# Foot_Controller.net
KiCad netlist of a schematic drawn in EAGLE
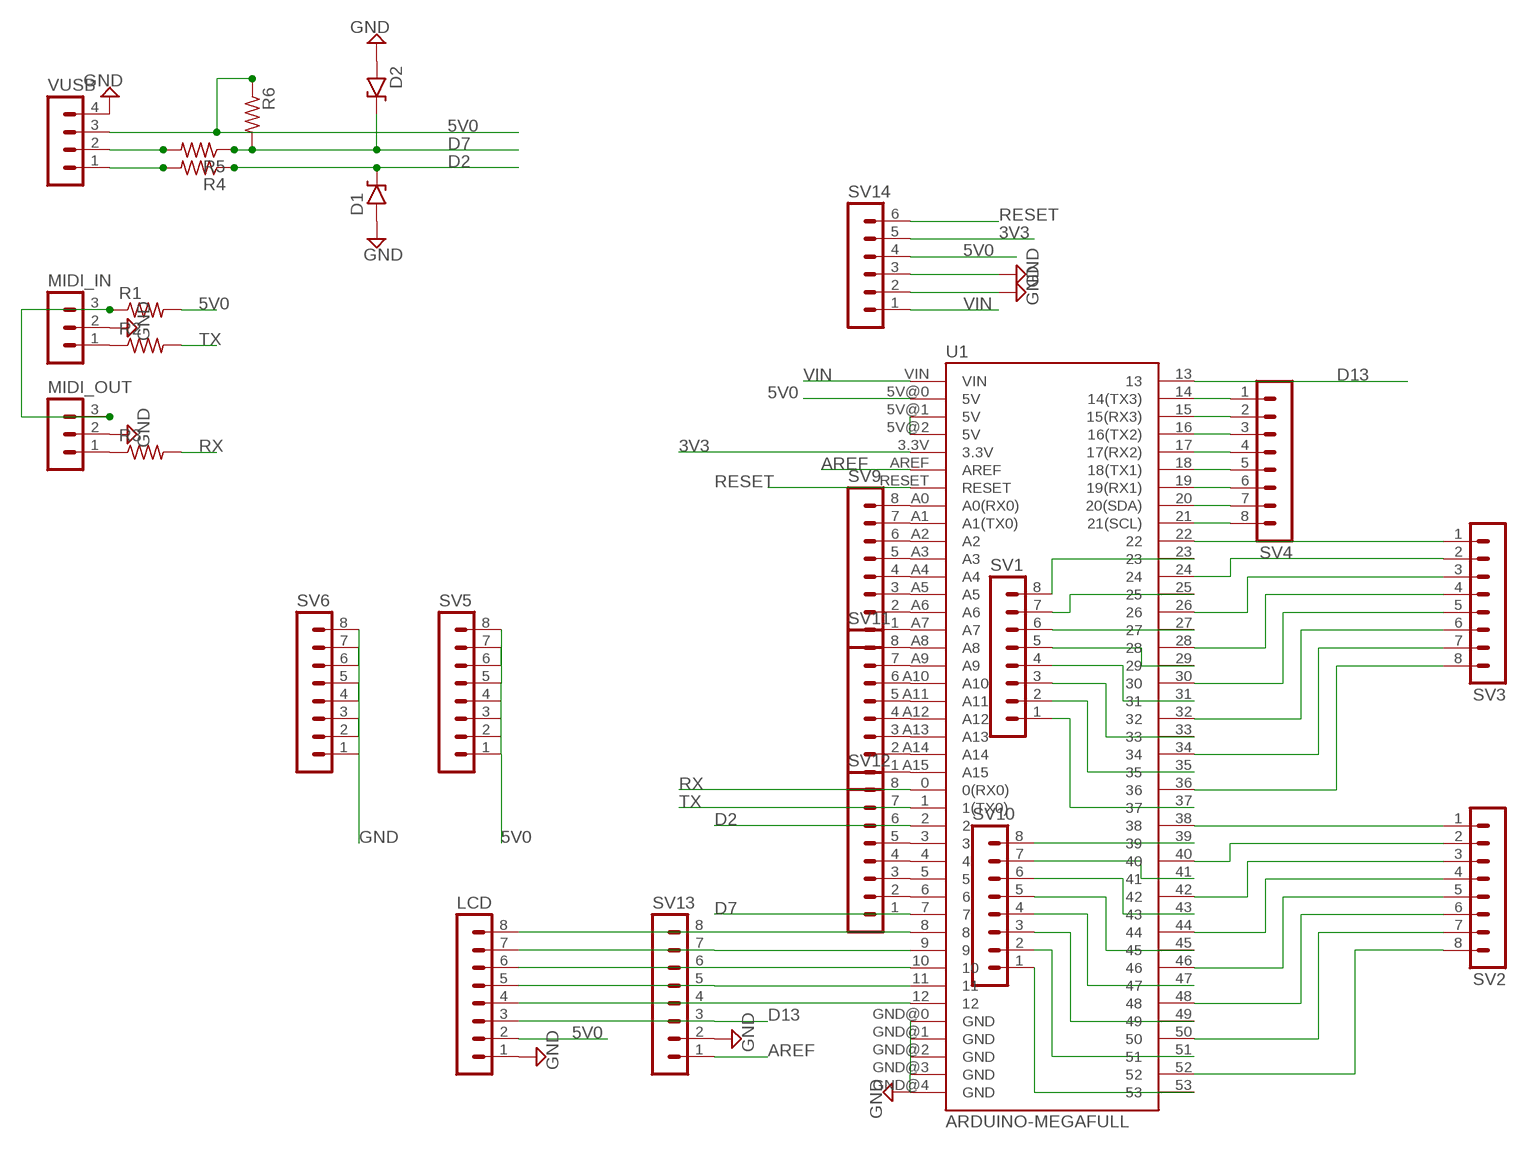
[diagram p0: schematic, sheet 1]

(export (version "E")
  (design (tool "Eeschema 10.0.6"))
  (components
    (comp (ref "D1")
      (value "1N9ZENER")
      (footprint "eagle-import:DO35-3")
      (libsource (lib "eagle-import") (part "1N9ZENER"))
    )
    (comp (ref "D2")
      (value "1N9ZENER")
      (footprint "eagle-import:DO35-3")
      (libsource (lib "eagle-import") (part "1N9ZENER"))
    )
    (comp (ref "LCD")
      (value "MA08-1")
      (footprint "eagle-import:MA08-1")
      (libsource (lib "eagle-import") (part "MA08-1"))
    )
    (comp (ref "MIDI_IN")
      (value "MA03-1")
      (footprint "eagle-import:MA03-1")
      (libsource (lib "eagle-import") (part "MA03-1"))
    )
    (comp (ref "MIDI_OUT")
      (value "MA03-1")
      (footprint "eagle-import:MA03-1")
      (libsource (lib "eagle-import") (part "MA03-1"))
    )
    (comp (ref "R1")
      (value "6MM.3")
      (footprint "eagle-import:R0207_3")
      (libsource (lib "eagle-import") (part "6MM.3"))
    )
    (comp (ref "R2")
      (value "6MM.3")
      (footprint "eagle-import:R0207_3")
      (libsource (lib "eagle-import") (part "6MM.3"))
    )
    (comp (ref "R3")
      (value "6MM.3")
      (footprint "eagle-import:R0207_3")
      (libsource (lib "eagle-import") (part "6MM.3"))
    )
    (comp (ref "R4")
      (value "6MM.3")
      (footprint "eagle-import:R0207_3")
      (libsource (lib "eagle-import") (part "6MM.3"))
    )
    (comp (ref "R5")
      (value "6MM.3")
      (footprint "eagle-import:R0207_3")
      (libsource (lib "eagle-import") (part "6MM.3"))
    )
    (comp (ref "R6")
      (value "6MM.3")
      (footprint "eagle-import:R0207_3")
      (libsource (lib "eagle-import") (part "6MM.3"))
    )
    (comp (ref "SV1")
      (value "MA08-1")
      (footprint "eagle-import:MA08-1")
      (libsource (lib "eagle-import") (part "MA08-1"))
    )
    (comp (ref "SV2")
      (value "MA08-1")
      (footprint "eagle-import:MA08-1")
      (libsource (lib "eagle-import") (part "MA08-1"))
    )
    (comp (ref "SV3")
      (value "MA08-1")
      (footprint "eagle-import:MA08-1")
      (libsource (lib "eagle-import") (part "MA08-1"))
    )
    (comp (ref "SV4")
      (value "MA08-1")
      (footprint "eagle-import:MA08-1")
      (libsource (lib "eagle-import") (part "MA08-1"))
    )
    (comp (ref "SV5")
      (value "MA08-1")
      (footprint "eagle-import:MA08-1")
      (libsource (lib "eagle-import") (part "MA08-1"))
    )
    (comp (ref "SV6")
      (value "MA08-1")
      (footprint "eagle-import:MA08-1")
      (libsource (lib "eagle-import") (part "MA08-1"))
    )
    (comp (ref "SV9")
      (value "MA08-1")
      (footprint "eagle-import:MA08-1")
      (libsource (lib "eagle-import") (part "MA08-1"))
    )
    (comp (ref "SV10")
      (value "MA08-1")
      (footprint "eagle-import:MA08-1")
      (libsource (lib "eagle-import") (part "MA08-1"))
    )
    (comp (ref "SV11")
      (value "MA08-1")
      (footprint "eagle-import:MA08-1")
      (libsource (lib "eagle-import") (part "MA08-1"))
    )
    (comp (ref "SV12")
      (value "MA08-1")
      (footprint "eagle-import:MA08-1")
      (libsource (lib "eagle-import") (part "MA08-1"))
    )
    (comp (ref "SV13")
      (value "MA08-1")
      (footprint "eagle-import:MA08-1")
      (libsource (lib "eagle-import") (part "MA08-1"))
    )
    (comp (ref "SV14")
      (value "MA06-1")
      (footprint "eagle-import:MA06-1")
      (libsource (lib "eagle-import") (part "MA06-1"))
    )
    (comp (ref "U1")
      (value "ARDUINO-MEGAFULL")
      (footprint "eagle-import:ARDUINO_MEGA")
      (libsource (lib "eagle-import") (part "ARDUINO-MEGAFULL"))
    )
    (comp (ref "VUSB")
      (value "MA04-1")
      (footprint "eagle-import:MA04-1")
      (libsource (lib "eagle-import") (part "MA04-1"))
    )
  )
  (nets
    (net (code "1") (name "/3V3") (class "Default")
      (node (ref "SV14") (pin "5") (pinfunction "5_5") (pintype "passive"))
      (node (ref "U1") (pin "3.3V") (pinfunction "3.3V_3.3V") (pintype "bidirectional"))
    )
    (net (code "2") (name "/5V0") (class "Default")
      (node (ref "LCD") (pin "2") (pinfunction "2_2") (pintype "passive"))
      (node (ref "R1") (pin "2") (pinfunction "2_2") (pintype "passive"))
      (node (ref "R6") (pin "1") (pinfunction "1_1") (pintype "passive"))
      (node (ref "SV14") (pin "4") (pinfunction "4_4") (pintype "passive"))
      (node (ref "SV5") (pin "1") (pinfunction "1_1") (pintype "passive"))
      (node (ref "SV5") (pin "2") (pinfunction "2_2") (pintype "passive"))
      (node (ref "SV5") (pin "3") (pinfunction "3_3") (pintype "passive"))
      (node (ref "SV5") (pin "4") (pinfunction "4_4") (pintype "passive"))
      (node (ref "SV5") (pin "5") (pinfunction "5_5") (pintype "passive"))
      (node (ref "SV5") (pin "6") (pinfunction "6_6") (pintype "passive"))
      (node (ref "SV5") (pin "7") (pinfunction "7_7") (pintype "passive"))
      (node (ref "SV5") (pin "8") (pinfunction "8_8") (pintype "passive"))
      (node (ref "U1") (pin "5V@0") (pinfunction "5V_5V@0") (pintype "bidirectional"))
      (node (ref "VUSB") (pin "3") (pinfunction "3_3") (pintype "passive"))
    )
    (net (code "3") (name "/AREF") (class "Default")
      (node (ref "SV13") (pin "1") (pinfunction "1_1") (pintype "passive"))
      (node (ref "U1") (pin "AREF") (pinfunction "AREF_AREF") (pintype "bidirectional"))
    )
    (net (code "4") (name "/D2") (class "Default")
      (node (ref "D1") (pin "C") (pinfunction "C_C") (pintype "passive"))
      (node (ref "R4") (pin "1") (pinfunction "1_1") (pintype "passive"))
      (node (ref "SV12") (pin "6") (pinfunction "6_6") (pintype "passive"))
      (node (ref "U1") (pin "2") (pinfunction "2_2") (pintype "bidirectional"))
    )
    (net (code "5") (name "/D7") (class "Default")
      (node (ref "D2") (pin "C") (pinfunction "C_C") (pintype "passive"))
      (node (ref "R5") (pin "1") (pinfunction "1_1") (pintype "passive"))
      (node (ref "R6") (pin "2") (pinfunction "2_2") (pintype "passive"))
      (node (ref "SV12") (pin "1") (pinfunction "1_1") (pintype "passive"))
      (node (ref "U1") (pin "7") (pinfunction "7_7") (pintype "bidirectional"))
    )
    (net (code "6") (name "/D13") (class "Default")
      (node (ref "LCD") (pin "3") (pinfunction "3_3") (pintype "passive"))
      (node (ref "SV13") (pin "3") (pinfunction "3_3") (pintype "passive"))
      (node (ref "U1") (pin "13") (pinfunction "13_13") (pintype "bidirectional"))
    )
    (net (code "7") (name "/RESET") (class "Default")
      (node (ref "SV14") (pin "6") (pinfunction "6_6") (pintype "passive"))
      (node (ref "U1") (pin "RESET") (pinfunction "RESET_RESET") (pintype "bidirectional"))
    )
    (net (code "8") (name "/RX") (class "Default")
      (node (ref "R3") (pin "2") (pinfunction "2_2") (pintype "passive"))
      (node (ref "SV12") (pin "8") (pinfunction "8_8") (pintype "passive"))
      (node (ref "U1") (pin "0") (pinfunction "0(RX0)_0") (pintype "bidirectional"))
    )
    (net (code "9") (name "/TX") (class "Default")
      (node (ref "R2") (pin "2") (pinfunction "2_2") (pintype "passive"))
      (node (ref "SV12") (pin "7") (pinfunction "7_7") (pintype "passive"))
      (node (ref "U1") (pin "1") (pinfunction "1(TX0)_1") (pintype "bidirectional"))
    )
    (net (code "10") (name "/VIN") (class "Default")
      (node (ref "SV14") (pin "1") (pinfunction "1_1") (pintype "passive"))
      (node (ref "U1") (pin "VIN") (pinfunction "VIN_VIN") (pintype "bidirectional"))
    )
    (net (code "11") (name "GND") (class "Default")
      (node (ref "D1") (pin "A") (pinfunction "A_A") (pintype "passive"))
      (node (ref "D2") (pin "A") (pinfunction "A_A") (pintype "passive"))
      (node (ref "LCD") (pin "1") (pinfunction "1_1") (pintype "passive"))
      (node (ref "MIDI_IN") (pin "2") (pinfunction "2_2") (pintype "passive"))
      (node (ref "MIDI_OUT") (pin "2") (pinfunction "2_2") (pintype "passive"))
      (node (ref "SV13") (pin "2") (pinfunction "2_2") (pintype "passive"))
      (node (ref "SV14") (pin "2") (pinfunction "2_2") (pintype "passive"))
      (node (ref "SV14") (pin "3") (pinfunction "3_3") (pintype "passive"))
      (node (ref "SV6") (pin "1") (pinfunction "1_1") (pintype "passive"))
      (node (ref "SV6") (pin "2") (pinfunction "2_2") (pintype "passive"))
      (node (ref "SV6") (pin "3") (pinfunction "3_3") (pintype "passive"))
      (node (ref "SV6") (pin "4") (pinfunction "4_4") (pintype "passive"))
      (node (ref "SV6") (pin "5") (pinfunction "5_5") (pintype "passive"))
      (node (ref "SV6") (pin "6") (pinfunction "6_6") (pintype "passive"))
      (node (ref "SV6") (pin "7") (pinfunction "7_7") (pintype "passive"))
      (node (ref "SV6") (pin "8") (pinfunction "8_8") (pintype "passive"))
      (node (ref "U1") (pin "GND@0") (pinfunction "GND_GND@0") (pintype "bidirectional"))
      (node (ref "U1") (pin "GND@1") (pinfunction "GND_GND@1") (pintype "bidirectional"))
      (node (ref "U1") (pin "GND@2") (pinfunction "GND_GND@2") (pintype "bidirectional"))
      (node (ref "U1") (pin "GND@3") (pinfunction "GND_GND@3") (pintype "bidirectional"))
      (node (ref "U1") (pin "GND@4") (pinfunction "GND_GND@4") (pintype "bidirectional"))
      (node (ref "VUSB") (pin "4") (pinfunction "4_4") (pintype "passive"))
    )
    (net (code "12") (name "Net-(LCD-Pad4)") (class "Default")
      (node (ref "LCD") (pin "4") (pinfunction "4_4") (pintype "passive"))
      (node (ref "SV13") (pin "4") (pinfunction "4_4") (pintype "passive"))
      (node (ref "U1") (pin "12") (pinfunction "12_12") (pintype "bidirectional"))
    )
    (net (code "13") (name "Net-(LCD-Pad5)") (class "Default")
      (node (ref "LCD") (pin "5") (pinfunction "5_5") (pintype "passive"))
      (node (ref "SV13") (pin "5") (pinfunction "5_5") (pintype "passive"))
      (node (ref "U1") (pin "11") (pinfunction "11_11") (pintype "bidirectional"))
    )
    (net (code "14") (name "Net-(LCD-Pad6)") (class "Default")
      (node (ref "LCD") (pin "6") (pinfunction "6_6") (pintype "passive"))
      (node (ref "SV13") (pin "6") (pinfunction "6_6") (pintype "passive"))
      (node (ref "U1") (pin "10") (pinfunction "10_10") (pintype "bidirectional"))
    )
    (net (code "15") (name "Net-(LCD-Pad7)") (class "Default")
      (node (ref "LCD") (pin "7") (pinfunction "7_7") (pintype "passive"))
      (node (ref "SV13") (pin "7") (pinfunction "7_7") (pintype "passive"))
      (node (ref "U1") (pin "9") (pinfunction "9_9") (pintype "bidirectional"))
    )
    (net (code "16") (name "Net-(LCD-Pad8)") (class "Default")
      (node (ref "LCD") (pin "8") (pinfunction "8_8") (pintype "passive"))
      (node (ref "SV13") (pin "8") (pinfunction "8_8") (pintype "passive"))
      (node (ref "U1") (pin "8") (pinfunction "8_8") (pintype "bidirectional"))
    )
    (net (code "17") (name "Net-(MIDI_IN-Pad1)") (class "Default")
      (node (ref "MIDI_IN") (pin "1") (pinfunction "1_1") (pintype "passive"))
      (node (ref "R2") (pin "1") (pinfunction "1_1") (pintype "passive"))
    )
    (net (code "18") (name "Net-(MIDI_IN-Pad3)") (class "Default")
      (node (ref "MIDI_IN") (pin "3") (pinfunction "3_3") (pintype "passive"))
      (node (ref "MIDI_OUT") (pin "3") (pinfunction "3_3") (pintype "passive"))
      (node (ref "R1") (pin "1") (pinfunction "1_1") (pintype "passive"))
    )
    (net (code "19") (name "Net-(MIDI_OUT-Pad1)") (class "Default")
      (node (ref "MIDI_OUT") (pin "1") (pinfunction "1_1") (pintype "passive"))
      (node (ref "R3") (pin "1") (pinfunction "1_1") (pintype "passive"))
    )
    (net (code "20") (name "Net-(R4-Pad2)") (class "Default")
      (node (ref "R4") (pin "2") (pinfunction "2_2") (pintype "passive"))
      (node (ref "VUSB") (pin "1") (pinfunction "1_1") (pintype "passive"))
    )
    (net (code "21") (name "Net-(R5-Pad2)") (class "Default")
      (node (ref "R5") (pin "2") (pinfunction "2_2") (pintype "passive"))
      (node (ref "VUSB") (pin "2") (pinfunction "2_2") (pintype "passive"))
    )
    (net (code "22") (name "Net-(SV1-Pad1)") (class "Default")
      (node (ref "SV1") (pin "1") (pinfunction "1_1") (pintype "passive"))
      (node (ref "U1") (pin "37") (pinfunction "37_37") (pintype "bidirectional"))
    )
    (net (code "23") (name "Net-(SV1-Pad2)") (class "Default")
      (node (ref "SV1") (pin "2") (pinfunction "2_2") (pintype "passive"))
      (node (ref "U1") (pin "35") (pinfunction "35_35") (pintype "bidirectional"))
    )
    (net (code "24") (name "Net-(SV1-Pad3)") (class "Default")
      (node (ref "SV1") (pin "3") (pinfunction "3_3") (pintype "passive"))
      (node (ref "U1") (pin "33") (pinfunction "33_33") (pintype "bidirectional"))
    )
    (net (code "25") (name "Net-(SV1-Pad4)") (class "Default")
      (node (ref "SV1") (pin "4") (pinfunction "4_4") (pintype "passive"))
      (node (ref "U1") (pin "31") (pinfunction "31_31") (pintype "bidirectional"))
    )
    (net (code "26") (name "Net-(SV1-Pad5)") (class "Default")
      (node (ref "SV1") (pin "5") (pinfunction "5_5") (pintype "passive"))
      (node (ref "U1") (pin "29") (pinfunction "29_29") (pintype "bidirectional"))
    )
    (net (code "27") (name "Net-(SV1-Pad6)") (class "Default")
      (node (ref "SV1") (pin "6") (pinfunction "6_6") (pintype "passive"))
      (node (ref "U1") (pin "27") (pinfunction "27_27") (pintype "bidirectional"))
    )
    (net (code "28") (name "Net-(SV1-Pad7)") (class "Default")
      (node (ref "SV1") (pin "7") (pinfunction "7_7") (pintype "passive"))
      (node (ref "U1") (pin "25") (pinfunction "25_25") (pintype "bidirectional"))
    )
    (net (code "29") (name "Net-(SV1-Pad8)") (class "Default")
      (node (ref "SV1") (pin "8") (pinfunction "8_8") (pintype "passive"))
      (node (ref "U1") (pin "23") (pinfunction "23_23") (pintype "bidirectional"))
    )
    (net (code "30") (name "Net-(SV2-Pad1)") (class "Default")
      (node (ref "SV2") (pin "1") (pinfunction "1_1") (pintype "passive"))
      (node (ref "U1") (pin "38") (pinfunction "38_38") (pintype "bidirectional"))
    )
    (net (code "31") (name "Net-(SV2-Pad2)") (class "Default")
      (node (ref "SV2") (pin "2") (pinfunction "2_2") (pintype "passive"))
      (node (ref "U1") (pin "40") (pinfunction "40_40") (pintype "bidirectional"))
    )
    (net (code "32") (name "Net-(SV2-Pad3)") (class "Default")
      (node (ref "SV2") (pin "3") (pinfunction "3_3") (pintype "passive"))
      (node (ref "U1") (pin "42") (pinfunction "42_42") (pintype "bidirectional"))
    )
    (net (code "33") (name "Net-(SV2-Pad4)") (class "Default")
      (node (ref "SV2") (pin "4") (pinfunction "4_4") (pintype "passive"))
      (node (ref "U1") (pin "44") (pinfunction "44_44") (pintype "bidirectional"))
    )
    (net (code "34") (name "Net-(SV2-Pad5)") (class "Default")
      (node (ref "SV2") (pin "5") (pinfunction "5_5") (pintype "passive"))
      (node (ref "U1") (pin "46") (pinfunction "46_46") (pintype "bidirectional"))
    )
    (net (code "35") (name "Net-(SV2-Pad6)") (class "Default")
      (node (ref "SV2") (pin "6") (pinfunction "6_6") (pintype "passive"))
      (node (ref "U1") (pin "48") (pinfunction "48_48") (pintype "bidirectional"))
    )
    (net (code "36") (name "Net-(SV2-Pad7)") (class "Default")
      (node (ref "SV2") (pin "7") (pinfunction "7_7") (pintype "passive"))
      (node (ref "U1") (pin "50") (pinfunction "50_50") (pintype "bidirectional"))
    )
    (net (code "37") (name "Net-(SV2-Pad8)") (class "Default")
      (node (ref "SV2") (pin "8") (pinfunction "8_8") (pintype "passive"))
      (node (ref "U1") (pin "52") (pinfunction "52_52") (pintype "bidirectional"))
    )
    (net (code "38") (name "Net-(SV3-Pad1)") (class "Default")
      (node (ref "SV3") (pin "1") (pinfunction "1_1") (pintype "passive"))
      (node (ref "U1") (pin "22") (pinfunction "22_22") (pintype "bidirectional"))
    )
    (net (code "39") (name "Net-(SV3-Pad2)") (class "Default")
      (node (ref "SV3") (pin "2") (pinfunction "2_2") (pintype "passive"))
      (node (ref "U1") (pin "24") (pinfunction "24_24") (pintype "bidirectional"))
    )
    (net (code "40") (name "Net-(SV3-Pad3)") (class "Default")
      (node (ref "SV3") (pin "3") (pinfunction "3_3") (pintype "passive"))
      (node (ref "U1") (pin "26") (pinfunction "26_26") (pintype "bidirectional"))
    )
    (net (code "41") (name "Net-(SV3-Pad4)") (class "Default")
      (node (ref "SV3") (pin "4") (pinfunction "4_4") (pintype "passive"))
      (node (ref "U1") (pin "28") (pinfunction "28_28") (pintype "bidirectional"))
    )
    (net (code "42") (name "Net-(SV3-Pad5)") (class "Default")
      (node (ref "SV3") (pin "5") (pinfunction "5_5") (pintype "passive"))
      (node (ref "U1") (pin "30") (pinfunction "30_30") (pintype "bidirectional"))
    )
    (net (code "43") (name "Net-(SV3-Pad6)") (class "Default")
      (node (ref "SV3") (pin "6") (pinfunction "6_6") (pintype "passive"))
      (node (ref "U1") (pin "32") (pinfunction "32_32") (pintype "bidirectional"))
    )
    (net (code "44") (name "Net-(SV3-Pad7)") (class "Default")
      (node (ref "SV3") (pin "7") (pinfunction "7_7") (pintype "passive"))
      (node (ref "U1") (pin "34") (pinfunction "34_34") (pintype "bidirectional"))
    )
    (net (code "45") (name "Net-(SV3-Pad8)") (class "Default")
      (node (ref "SV3") (pin "8") (pinfunction "8_8") (pintype "passive"))
      (node (ref "U1") (pin "36") (pinfunction "36_36") (pintype "bidirectional"))
    )
    (net (code "46") (name "Net-(SV9-Pad1)") (class "Default")
      (node (ref "SV9") (pin "1") (pinfunction "1_1") (pintype "passive"))
      (node (ref "U1") (pin "A7") (pinfunction "A7_A7") (pintype "bidirectional"))
    )
    (net (code "47") (name "Net-(SV9-Pad2)") (class "Default")
      (node (ref "SV9") (pin "2") (pinfunction "2_2") (pintype "passive"))
      (node (ref "U1") (pin "A6") (pinfunction "A6_A6") (pintype "bidirectional"))
    )
    (net (code "48") (name "Net-(SV9-Pad3)") (class "Default")
      (node (ref "SV9") (pin "3") (pinfunction "3_3") (pintype "passive"))
      (node (ref "U1") (pin "A5") (pinfunction "A5_A5") (pintype "bidirectional"))
    )
    (net (code "49") (name "Net-(SV9-Pad4)") (class "Default")
      (node (ref "SV9") (pin "4") (pinfunction "4_4") (pintype "passive"))
      (node (ref "U1") (pin "A4") (pinfunction "A4_A4") (pintype "bidirectional"))
    )
    (net (code "50") (name "Net-(SV9-Pad5)") (class "Default")
      (node (ref "SV9") (pin "5") (pinfunction "5_5") (pintype "passive"))
      (node (ref "U1") (pin "A3") (pinfunction "A3_A3") (pintype "bidirectional"))
    )
    (net (code "51") (name "Net-(SV9-Pad6)") (class "Default")
      (node (ref "SV9") (pin "6") (pinfunction "6_6") (pintype "passive"))
      (node (ref "U1") (pin "A2") (pinfunction "A2_A2") (pintype "bidirectional"))
    )
    (net (code "52") (name "Net-(SV10-Pad1)") (class "Default")
      (node (ref "SV10") (pin "1") (pinfunction "1_1") (pintype "passive"))
      (node (ref "U1") (pin "53") (pinfunction "53_53") (pintype "bidirectional"))
    )
    (net (code "53") (name "Net-(SV10-Pad2)") (class "Default")
      (node (ref "SV10") (pin "2") (pinfunction "2_2") (pintype "passive"))
      (node (ref "U1") (pin "51") (pinfunction "51_51") (pintype "bidirectional"))
    )
    (net (code "54") (name "Net-(SV10-Pad3)") (class "Default")
      (node (ref "SV10") (pin "3") (pinfunction "3_3") (pintype "passive"))
      (node (ref "U1") (pin "49") (pinfunction "49_49") (pintype "bidirectional"))
    )
    (net (code "55") (name "Net-(SV10-Pad4)") (class "Default")
      (node (ref "SV10") (pin "4") (pinfunction "4_4") (pintype "passive"))
      (node (ref "U1") (pin "47") (pinfunction "47_47") (pintype "bidirectional"))
    )
    (net (code "56") (name "Net-(SV10-Pad5)") (class "Default")
      (node (ref "SV10") (pin "5") (pinfunction "5_5") (pintype "passive"))
      (node (ref "U1") (pin "45") (pinfunction "45_45") (pintype "bidirectional"))
    )
    (net (code "57") (name "Net-(SV10-Pad6)") (class "Default")
      (node (ref "SV10") (pin "6") (pinfunction "6_6") (pintype "passive"))
      (node (ref "U1") (pin "43") (pinfunction "43_43") (pintype "bidirectional"))
    )
    (net (code "58") (name "Net-(SV10-Pad7)") (class "Default")
      (node (ref "SV10") (pin "7") (pinfunction "7_7") (pintype "passive"))
      (node (ref "U1") (pin "41") (pinfunction "41_41") (pintype "bidirectional"))
    )
    (net (code "59") (name "Net-(SV10-Pad8)") (class "Default")
      (node (ref "SV10") (pin "8") (pinfunction "8_8") (pintype "passive"))
      (node (ref "U1") (pin "39") (pinfunction "39_39") (pintype "bidirectional"))
    )
    (net (code "60") (name "Net-(SV11-Pad1)") (class "Default")
      (node (ref "SV11") (pin "1") (pinfunction "1_1") (pintype "passive"))
      (node (ref "U1") (pin "A15") (pinfunction "A15_A15") (pintype "bidirectional"))
    )
    (net (code "61") (name "Net-(SV11-Pad2)") (class "Default")
      (node (ref "SV11") (pin "2") (pinfunction "2_2") (pintype "passive"))
      (node (ref "U1") (pin "A14") (pinfunction "A14_A14") (pintype "bidirectional"))
    )
    (net (code "62") (name "Net-(SV11-Pad3)") (class "Default")
      (node (ref "SV11") (pin "3") (pinfunction "3_3") (pintype "passive"))
      (node (ref "U1") (pin "A13") (pinfunction "A13_A13") (pintype "bidirectional"))
    )
    (net (code "63") (name "Net-(SV11-Pad4)") (class "Default")
      (node (ref "SV11") (pin "4") (pinfunction "4_4") (pintype "passive"))
      (node (ref "U1") (pin "A12") (pinfunction "A12_A12") (pintype "bidirectional"))
    )
    (net (code "64") (name "Net-(SV11-Pad5)") (class "Default")
      (node (ref "SV11") (pin "5") (pinfunction "5_5") (pintype "passive"))
      (node (ref "U1") (pin "A11") (pinfunction "A11_A11") (pintype "bidirectional"))
    )
    (net (code "65") (name "Net-(SV11-Pad6)") (class "Default")
      (node (ref "SV11") (pin "6") (pinfunction "6_6") (pintype "passive"))
      (node (ref "U1") (pin "A10") (pinfunction "A10_A10") (pintype "bidirectional"))
    )
    (net (code "66") (name "Net-(SV11-Pad7)") (class "Default")
      (node (ref "SV11") (pin "7") (pinfunction "7_7") (pintype "passive"))
      (node (ref "U1") (pin "A9") (pinfunction "A9_A9") (pintype "bidirectional"))
    )
    (net (code "67") (name "Net-(SV11-Pad8)") (class "Default")
      (node (ref "SV11") (pin "8") (pinfunction "8_8") (pintype "passive"))
      (node (ref "U1") (pin "A8") (pinfunction "A8_A8") (pintype "bidirectional"))
    )
    (net (code "68") (name "Net-(SV12-Pad2)") (class "Default")
      (node (ref "SV12") (pin "2") (pinfunction "2_2") (pintype "passive"))
      (node (ref "U1") (pin "6") (pinfunction "6_6") (pintype "bidirectional"))
    )
    (net (code "69") (name "Net-(SV12-Pad3)") (class "Default")
      (node (ref "SV12") (pin "3") (pinfunction "3_3") (pintype "passive"))
      (node (ref "U1") (pin "5") (pinfunction "5_5") (pintype "bidirectional"))
    )
    (net (code "70") (name "Net-(SV12-Pad4)") (class "Default")
      (node (ref "SV12") (pin "4") (pinfunction "4_4") (pintype "passive"))
      (node (ref "U1") (pin "4") (pinfunction "4_4") (pintype "bidirectional"))
    )
    (net (code "71") (name "Net-(SV12-Pad5)") (class "Default")
      (node (ref "SV12") (pin "5") (pinfunction "5_5") (pintype "passive"))
      (node (ref "U1") (pin "3") (pinfunction "3_3") (pintype "bidirectional"))
    )
    (net (code "72") (name "Net-(U1-5V-Pad5V@1)") (class "Default")
      (node (ref "U1") (pin "5V@1") (pinfunction "5V_5V@1") (pintype "bidirectional"))
      (node (ref "U1") (pin "5V@2") (pinfunction "5V_5V@2") (pintype "bidirectional"))
    )
    (net (code "73") (name "Net-(U1-14(TX3))") (class "Default")
      (node (ref "SV4") (pin "1") (pinfunction "1_1") (pintype "passive"))
      (node (ref "U1") (pin "14") (pinfunction "14(TX3)_14") (pintype "bidirectional"))
    )
    (net (code "74") (name "Net-(U1-15(RX3))") (class "Default")
      (node (ref "SV4") (pin "2") (pinfunction "2_2") (pintype "passive"))
      (node (ref "U1") (pin "15") (pinfunction "15(RX3)_15") (pintype "bidirectional"))
    )
    (net (code "75") (name "Net-(U1-16(TX2))") (class "Default")
      (node (ref "SV4") (pin "3") (pinfunction "3_3") (pintype "passive"))
      (node (ref "U1") (pin "16") (pinfunction "16(TX2)_16") (pintype "bidirectional"))
    )
    (net (code "76") (name "Net-(U1-17(RX2))") (class "Default")
      (node (ref "SV4") (pin "4") (pinfunction "4_4") (pintype "passive"))
      (node (ref "U1") (pin "17") (pinfunction "17(RX2)_17") (pintype "bidirectional"))
    )
    (net (code "77") (name "Net-(U1-18(TX1))") (class "Default")
      (node (ref "SV4") (pin "5") (pinfunction "5_5") (pintype "passive"))
      (node (ref "U1") (pin "18") (pinfunction "18(TX1)_18") (pintype "bidirectional"))
    )
    (net (code "78") (name "Net-(U1-19(RX1))") (class "Default")
      (node (ref "SV4") (pin "6") (pinfunction "6_6") (pintype "passive"))
      (node (ref "U1") (pin "19") (pinfunction "19(RX1)_19") (pintype "bidirectional"))
    )
    (net (code "79") (name "Net-(U1-20(SDA))") (class "Default")
      (node (ref "SV4") (pin "7") (pinfunction "7_7") (pintype "passive"))
      (node (ref "U1") (pin "20") (pinfunction "20(SDA)_20") (pintype "bidirectional"))
    )
    (net (code "80") (name "Net-(U1-21(SCL))") (class "Default")
      (node (ref "SV4") (pin "8") (pinfunction "8_8") (pintype "passive"))
      (node (ref "U1") (pin "21") (pinfunction "21(SCL)_21") (pintype "bidirectional"))
    )
    (net (code "81") (name "Net-(U1-A0(RX0))") (class "Default")
      (node (ref "SV9") (pin "8") (pinfunction "8_8") (pintype "passive"))
      (node (ref "U1") (pin "A0") (pinfunction "A0(RX0)_A0") (pintype "bidirectional"))
    )
    (net (code "82") (name "Net-(U1-A1(TX0))") (class "Default")
      (node (ref "SV9") (pin "7") (pinfunction "7_7") (pintype "passive"))
      (node (ref "U1") (pin "A1") (pinfunction "A1(TX0)_A1") (pintype "bidirectional"))
    )
  )
)
